# USB_power_converter.net
KiCad netlist of a schematic drawn in EAGLE
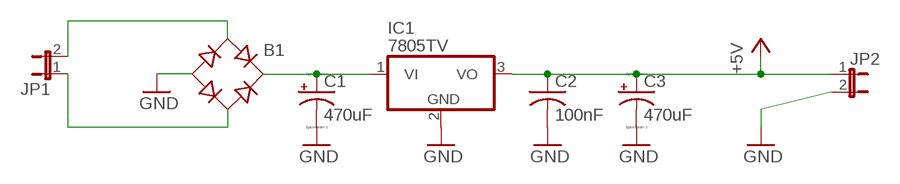
[diagram p0: schematic, sheet 1]

(export (version "E")
  (design (tool "Eeschema 10.0.6"))
  (components
    (comp (ref "B1")
      (value "RB1A")
      (footprint "eagle-import:RB1A")
      (libsource (lib "eagle-import") (part "RB1A"))
    )
    (comp (ref "C1")
      (value "470uF")
      (footprint "eagle-import:E3,5-8")
      (libsource (lib "eagle-import") (part "CPOL-USE3.5-8"))
    )
    (comp (ref "C2")
      (value "100nF")
      (footprint "eagle-import:C025-024X044")
      (libsource (lib "eagle-import") (part "C-US025-024X044"))
    )
    (comp (ref "C3")
      (value "470uF")
      (footprint "eagle-import:E3,5-8")
      (libsource (lib "eagle-import") (part "CPOL-USE3.5-8"))
    )
    (comp (ref "IC1")
      (value "7805TV")
      (footprint "eagle-import:TO220V")
      (libsource (lib "eagle-import") (part "78TV05"))
    )
    (comp (ref "JP1")
      (value "JP1E")
      (footprint "eagle-import:JP1")
      (libsource (lib "eagle-import") (part "JP1E"))
    )
    (comp (ref "JP2")
      (value "JP1E")
      (footprint "eagle-import:JP1")
      (libsource (lib "eagle-import") (part "JP1E"))
    )
  )
  (nets
    (net (code "1") (name "+5V") (class "Default")
      (node (ref "C2") (pin "1") (pinfunction "1_1") (pintype "passive"))
      (node (ref "C3") (pin "+") (pinfunction "+_+") (pintype "passive"))
      (node (ref "IC1") (pin "3") (pinfunction "VO_3") (pintype "passive"))
      (node (ref "JP2") (pin "1") (pinfunction "1_1") (pintype "passive"))
    )
    (net (code "2") (name "GND") (class "Default")
      (node (ref "B1") (pin "-") (pinfunction "-_-") (pintype "passive"))
      (node (ref "C1") (pin "-") (pinfunction "-_-") (pintype "passive"))
      (node (ref "C2") (pin "2") (pinfunction "2_2") (pintype "passive"))
      (node (ref "C3") (pin "-") (pinfunction "-_-") (pintype "passive"))
      (node (ref "IC1") (pin "2") (pinfunction "GND_2") (pintype "passive"))
      (node (ref "JP2") (pin "2") (pinfunction "2_2") (pintype "passive"))
    )
    (net (code "3") (name "Net-(B1-PadAC1)") (class "Default")
      (node (ref "B1") (pin "AC1") (pinfunction "AC1_AC1") (pintype "passive"))
      (node (ref "JP1") (pin "2") (pinfunction "2_2") (pintype "passive"))
    )
    (net (code "4") (name "Net-(B1-PadAC2)") (class "Default")
      (node (ref "B1") (pin "AC2") (pinfunction "AC2_AC2") (pintype "passive"))
      (node (ref "JP1") (pin "1") (pinfunction "1_1") (pintype "passive"))
    )
    (net (code "5") (name "Net-(IC1-VI)") (class "Default")
      (node (ref "B1") (pin "+") (pinfunction "+_+") (pintype "passive"))
      (node (ref "C1") (pin "+") (pinfunction "+_+") (pintype "passive"))
      (node (ref "IC1") (pin "1") (pinfunction "VI_1") (pintype "input"))
    )
  )
)
